# 01_detection_tdc.net
KiCad netlist of a schematic drawn in Altium Designer
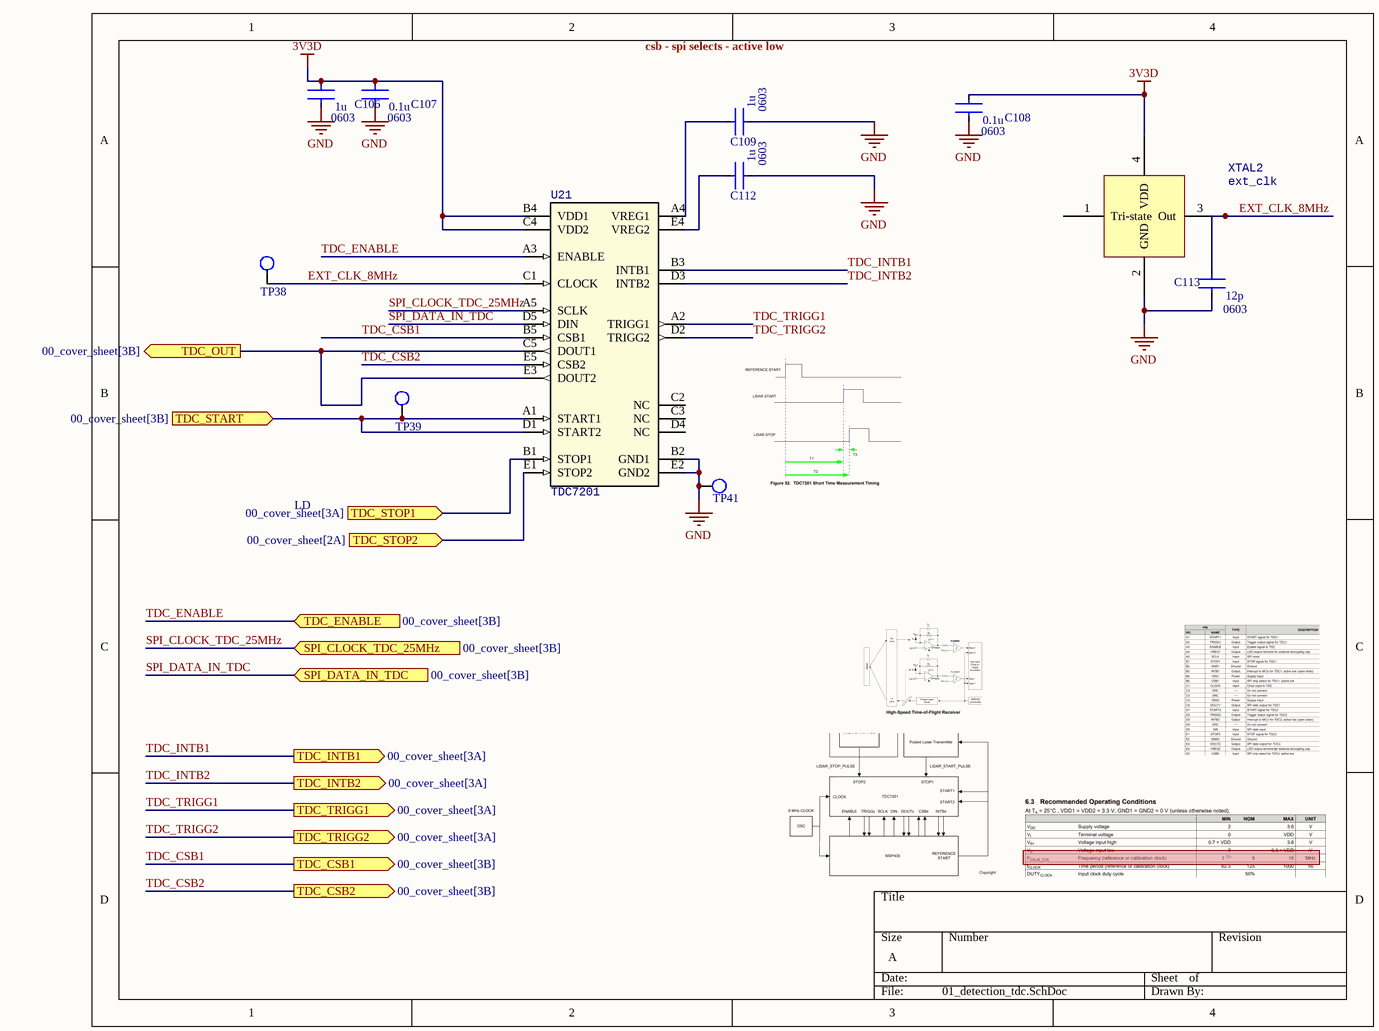
[diagram p0: 01_detection_tdc.SchDoc]

(export (version "E")
  (design (tool "Eeschema 10.0.6"))
  (components
    (comp (ref "C106")
      (value "C1608X5R1E105K080AC")
      (footprint "CAPTDK0603")
      (description "CAP CER 1UF 25V X5R 0603")
      (libsource (lib "tcspc00") (part "C1608X5R1E105K080AC"))
    )
    (comp (ref "C107")
      (value "CGA3E2X7R1H104K080AA")
      (footprint "CAPTDK0603")
      (description "CAP CER 0.1UF 50V X7R 0603")
      (libsource (lib "tcspc00") (part "CGA3E2X7R1H104K080AA"))
    )
    (comp (ref "C108")
      (value "CGA3E2X7R1H104K080AA")
      (footprint "CAPTDK0603")
      (description "CAP CER 0.1UF 50V X7R 0603")
      (libsource (lib "tcspc00") (part "CGA3E2X7R1H104K080AA"))
    )
    (comp (ref "C109")
      (value "C1608X5R1E105K080AC")
      (footprint "CAPTDK0603")
      (description "CAP CER 1UF 25V X5R 0603")
      (libsource (lib "tcspc00") (part "C1608X5R1E105K080AC"))
    )
    (comp (ref "C112")
      (value "C1608X5R1E105K080AC")
      (footprint "CAPTDK0603")
      (description "CAP CER 1UF 25V X5R 0603")
      (libsource (lib "tcspc00") (part "C1608X5R1E105K080AC"))
    )
    (comp (ref "C113")
      (value "CGA3E2C0G1H120J080AA")
      (footprint "CAPTDK0603")
      (description "CAP CER 12PF 50V C0G 0603")
      (libsource (lib "tcspc00") (part "CGA3E2C0G1H120J080AA"))
    )
    (comp (ref "TP38")
      (value "TESTPOINT_S")
      (footprint "TESTPOINT_S")
      (description "Testpoint Surface Pad")
      (libsource (lib "tcspc00") (part "TESTPOINT_S"))
    )
    (comp (ref "TP39")
      (value "TESTPOINT_S")
      (footprint "TESTPOINT_S")
      (description "Testpoint Surface Pad")
      (libsource (lib "tcspc00") (part "TESTPOINT_S"))
    )
    (comp (ref "TP41")
      (value "TESTPOINT_S")
      (footprint "TESTPOINT_S")
      (description "Testpoint Surface Pad")
      (libsource (lib "tcspc00") (part "TESTPOINT_S"))
    )
    (comp (ref "U21")
      (value "TDC7201")
      (footprint "ZAX0025A")
      (description "IC TIME TO DIGITAL CONV 25-NFBGA")
      (libsource (lib "tcspc00") (part "TDC7201"))
    )
    (comp (ref "XTAL2")
      (value "ext_clk")
      (footprint "ECS-2520MV")
      (description "OSC XO 16.0000MHZ CMOS SMD")
      (libsource (lib "tcspc00") (part "ECS-2520MV-160-CN-TR"))
    )
  )
  (nets
    (net (code "1") (name "/EXT_CLK_8MHz") (class "Default")
      (node (ref "C113") (pin "1") (pinfunction "1_1") (pintype "passive"))
      (node (ref "TP38") (pin "1") (pinfunction "1_1") (pintype "passive"))
      (node (ref "U21") (pin "C1") (pinfunction "CLOCK_C1") (pintype "input"))
      (node (ref "XTAL2") (pin "3") (pinfunction "Out_3") (pintype "passive"))
    )
    (net (code "2") (name "/SPI_CLOCK_TDC_25MHz") (class "Default")
      (node (ref "U21") (pin "A5") (pinfunction "SCLK_A5") (pintype "input"))
    )
    (net (code "3") (name "/SPI_DATA_IN_TDC") (class "Default")
      (node (ref "U21") (pin "D5") (pinfunction "DIN_D5") (pintype "input"))
    )
    (net (code "4") (name "/TDC_CSB1") (class "Default")
      (node (ref "U21") (pin "B5") (pinfunction "CSB1_B5") (pintype "input"))
    )
    (net (code "5") (name "/TDC_CSB2") (class "Default")
      (node (ref "U21") (pin "E5") (pinfunction "CSB2_E5") (pintype "input"))
    )
    (net (code "6") (name "/TDC_ENABLE") (class "Default")
      (node (ref "U21") (pin "A3") (pinfunction "ENABLE_A3") (pintype "input"))
    )
    (net (code "7") (name "/TDC_INTB1") (class "Default")
      (node (ref "U21") (pin "B3") (pinfunction "INTB1_B3") (pintype "open_collector"))
    )
    (net (code "8") (name "/TDC_INTB2") (class "Default")
      (node (ref "U21") (pin "D3") (pinfunction "INTB2_D3") (pintype "open_collector"))
    )
    (net (code "9") (name "/TDC_OUT") (class "Default")
      (node (ref "U21") (pin "C5") (pinfunction "DOUT1_C5") (pintype "output"))
      (node (ref "U21") (pin "E3") (pinfunction "DOUT2_E3") (pintype "output"))
    )
    (net (code "10") (name "/TDC_START") (class "Default")
      (node (ref "TP39") (pin "1") (pinfunction "1_1") (pintype "passive"))
      (node (ref "U21") (pin "A1") (pinfunction "START1_A1") (pintype "input"))
      (node (ref "U21") (pin "D1") (pinfunction "START2_D1") (pintype "input"))
    )
    (net (code "11") (name "/TDC_STOP1") (class "Default")
      (node (ref "U21") (pin "B1") (pinfunction "STOP1_B1") (pintype "input"))
    )
    (net (code "12") (name "/TDC_STOP2") (class "Default")
      (node (ref "U21") (pin "E1") (pinfunction "STOP2_E1") (pintype "input"))
    )
    (net (code "13") (name "/TDC_TRIGG1") (class "Default")
      (node (ref "U21") (pin "A2") (pinfunction "TRIGG1_A2") (pintype "output"))
    )
    (net (code "14") (name "/TDC_TRIGG2") (class "Default")
      (node (ref "U21") (pin "D2") (pinfunction "TRIGG2_D2") (pintype "output"))
    )
    (net (code "15") (name "3V3D") (class "Default")
      (node (ref "C106") (pin "1") (pinfunction "1_1") (pintype "passive"))
      (node (ref "C107") (pin "1") (pinfunction "1_1") (pintype "passive"))
      (node (ref "C108") (pin "1") (pinfunction "1_1") (pintype "passive"))
      (node (ref "U21") (pin "B4") (pinfunction "VDD1_B4") (pintype "power_in"))
      (node (ref "U21") (pin "C4") (pinfunction "VDD2_C4") (pintype "power_in"))
      (node (ref "XTAL2") (pin "4") (pinfunction "VDD_4") (pintype "passive"))
    )
    (net (code "16") (name "GND") (class "Default")
      (node (ref "C106") (pin "2") (pinfunction "2_2") (pintype "passive"))
      (node (ref "C107") (pin "2") (pinfunction "2_2") (pintype "passive"))
      (node (ref "C108") (pin "2") (pinfunction "2_2") (pintype "passive"))
      (node (ref "C109") (pin "2") (pinfunction "2_2") (pintype "passive"))
      (node (ref "C112") (pin "2") (pinfunction "2_2") (pintype "passive"))
      (node (ref "C113") (pin "2") (pinfunction "2_2") (pintype "passive"))
      (node (ref "TP41") (pin "1") (pinfunction "1_1") (pintype "passive"))
      (node (ref "U21") (pin "B2") (pinfunction "GND1_B2") (pintype "power_in"))
      (node (ref "U21") (pin "E2") (pinfunction "GND2_E2") (pintype "power_in"))
      (node (ref "XTAL2") (pin "2") (pinfunction "GND_2") (pintype "passive"))
    )
    (net (code "17") (name "Net-(U21-VREG1)") (class "Default")
      (node (ref "C109") (pin "1") (pinfunction "1_1") (pintype "passive"))
      (node (ref "U21") (pin "A4") (pinfunction "VREG1_A4") (pintype "power_in"))
    )
    (net (code "18") (name "Net-(U21-VREG2)") (class "Default")
      (node (ref "C112") (pin "1") (pinfunction "1_1") (pintype "passive"))
      (node (ref "U21") (pin "E4") (pinfunction "VREG2_E4") (pintype "power_in"))
    )
    (net (code "19") (name "unconnected-(U21-NC-PadC2)") (class "Default")
      (node (ref "U21") (pin "C2") (pinfunction "NC_C2") (pintype "passive"))
    )
    (net (code "20") (name "unconnected-(U21-NC-PadC3)") (class "Default")
      (node (ref "U21") (pin "C3") (pinfunction "NC_C3") (pintype "passive"))
    )
    (net (code "21") (name "unconnected-(U21-NC-PadD4)") (class "Default")
      (node (ref "U21") (pin "D4") (pinfunction "NC_D4") (pintype "passive"))
    )
    (net (code "22") (name "unconnected-(XTAL2-Tri-state-Pad1)") (class "Default")
      (node (ref "XTAL2") (pin "1") (pinfunction "Tri-state_1") (pintype "passive"))
    )
  )
)
